# WS2812B-HueStrip-single.net
KiCad netlist of a schematic drawn in EAGLE
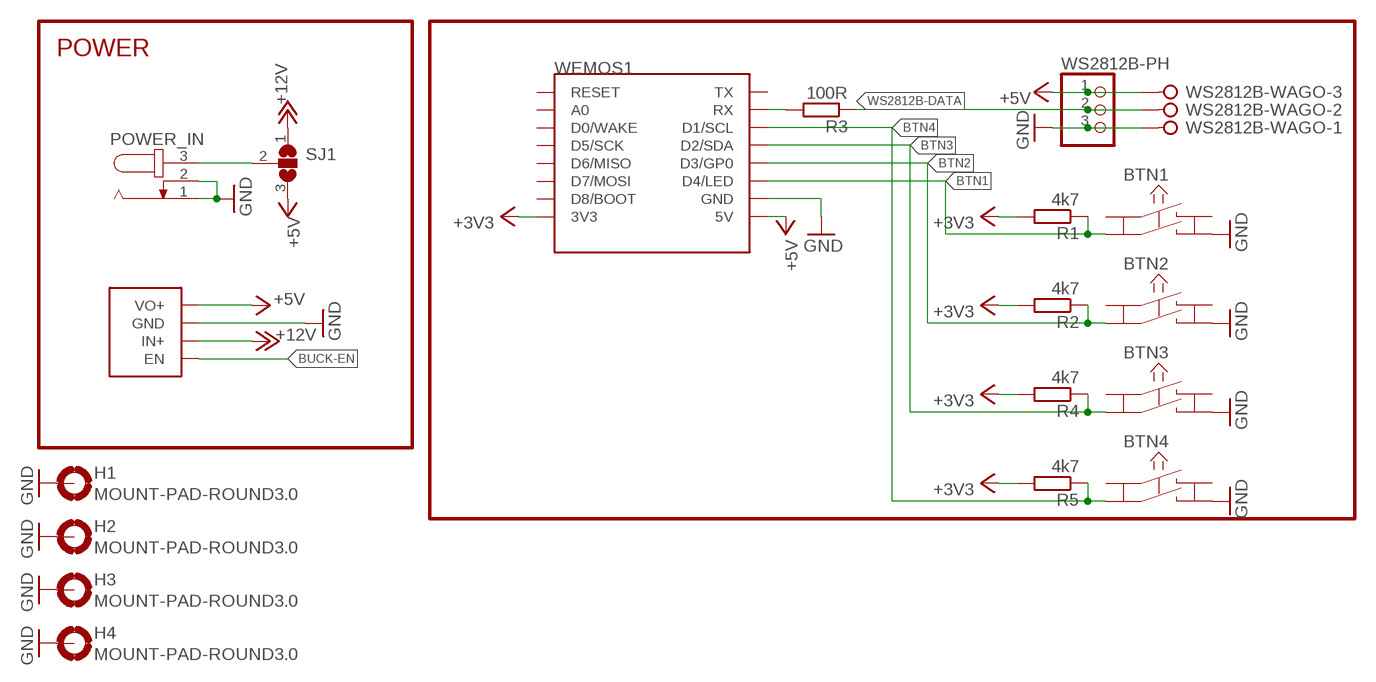
[diagram p0: schematic, sheet 1]

(export (version "E")
  (design (tool "Eeschema 10.0.6"))
  (components
    (comp (ref "BTN1")
      (value "KSM611A")
      (footprint "eagle-import:KSM611A")
      (libsource (lib "eagle-import") (part "KSM611A"))
    )
    (comp (ref "BTN2")
      (value "KSM611A")
      (footprint "eagle-import:KSM611A")
      (libsource (lib "eagle-import") (part "KSM611A"))
    )
    (comp (ref "BTN3")
      (value "KSM611A")
      (footprint "eagle-import:KSM611A")
      (libsource (lib "eagle-import") (part "KSM611A"))
    )
    (comp (ref "BTN4")
      (value "KSM611A")
      (footprint "eagle-import:KSM611A")
      (libsource (lib "eagle-import") (part "KSM611A"))
    )
    (comp (ref "H1")
      (value "MOUNT-PAD-ROUND3.0")
      (footprint "eagle-import:3,0-PAD")
      (libsource (lib "eagle-import") (part "MOUNT-PAD-ROUND3.0"))
    )
    (comp (ref "H2")
      (value "MOUNT-PAD-ROUND3.0")
      (footprint "eagle-import:3,0-PAD")
      (libsource (lib "eagle-import") (part "MOUNT-PAD-ROUND3.0"))
    )
    (comp (ref "H3")
      (value "MOUNT-PAD-ROUND3.0")
      (footprint "eagle-import:3,0-PAD")
      (libsource (lib "eagle-import") (part "MOUNT-PAD-ROUND3.0"))
    )
    (comp (ref "H4")
      (value "MOUNT-PAD-ROUND3.0")
      (footprint "eagle-import:3,0-PAD")
      (libsource (lib "eagle-import") (part "MOUNT-PAD-ROUND3.0"))
    )
    (comp (ref "POWER_IN")
      (value "RAPC7120")
      (footprint "eagle-import:RAPC712")
      (libsource (lib "eagle-import") (part "RAPC7120"))
    )
    (comp (ref "R1")
      (value "4k7")
      (footprint "eagle-import:0204_7")
      (libsource (lib "eagle-import") (part "R-EU_0204/7"))
    )
    (comp (ref "R2")
      (value "4k7")
      (footprint "eagle-import:0204_7")
      (libsource (lib "eagle-import") (part "R-EU_0204/7"))
    )
    (comp (ref "R3")
      (value "100R")
      (footprint "eagle-import:0204_7")
      (libsource (lib "eagle-import") (part "R-EU_0204/7"))
    )
    (comp (ref "R4")
      (value "4k7")
      (footprint "eagle-import:0204_7")
      (libsource (lib "eagle-import") (part "R-EU_0204/7"))
    )
    (comp (ref "R5")
      (value "4k7")
      (footprint "eagle-import:0204_7")
      (libsource (lib "eagle-import") (part "R-EU_0204/7"))
    )
    (comp (ref "SJ1")
      (value "SJ2WW")
      (footprint "eagle-import:SJ_2W")
      (libsource (lib "eagle-import") (part "SJ2WW"))
    )
    (comp (ref "U$1")
      (value "BUCK_CONVERTER_TE818")
      (footprint "eagle-import:BUCK_CONVERTER_TE818")
      (libsource (lib "eagle-import") (part "BUCK_CONVERTER_TE818"))
    )
    (comp (ref "WEMOS1")
      (value "WEMOS-D1-MINI")
      (footprint "eagle-import:WEMOS-D1-MINI")
      (libsource (lib "eagle-import") (part "WEMOS-D1-MINI"))
    )
    (comp (ref "WS2812B-PH")
      (value "PINHD-1X03_2.54-S")
      (footprint "eagle-import:1X03-S")
      (libsource (lib "eagle-import") (part "PINHD-1X03_2.54-S"))
    )
    (comp (ref "WS2812B-WAGO")
      (value "W237-3E")
      (footprint "eagle-import:W237-3E")
      (libsource (lib "eagle-import") (part "W237-3E"))
    )
  )
  (nets
    (net (code "1") (name "+3V3") (class "Default")
      (node (ref "R1") (pin "2") (pinfunction "2_2") (pintype "passive"))
      (node (ref "R2") (pin "2") (pinfunction "2_2") (pintype "passive"))
      (node (ref "R4") (pin "2") (pinfunction "2_2") (pintype "passive"))
      (node (ref "R5") (pin "2") (pinfunction "2_2") (pintype "passive"))
      (node (ref "WEMOS1") (pin "3V3") (pinfunction "3V3_3V3") (pintype "bidirectional"))
    )
    (net (code "2") (name "+5V") (class "Default")
      (node (ref "SJ1") (pin "3") (pinfunction "3_3") (pintype "passive"))
      (node (ref "U$1") (pin "VO+") (pinfunction "VO+_VO+") (pintype "bidirectional"))
      (node (ref "WEMOS1") (pin "5V") (pinfunction "5V_5V") (pintype "bidirectional"))
      (node (ref "WS2812B-PH") (pin "1") (pinfunction "1_1") (pintype "passive"))
      (node (ref "WS2812B-WAGO") (pin "3") (pinfunction "KL_3") (pintype "passive"))
    )
    (net (code "3") (name "+12V") (class "Default")
      (node (ref "SJ1") (pin "1") (pinfunction "1_1") (pintype "passive"))
      (node (ref "U$1") (pin "IN+") (pinfunction "IN+_IN+") (pintype "bidirectional"))
    )
    (net (code "4") (name "BTN1") (class "Default")
      (node (ref "BTN1") (pin "C") (pinfunction "C_C") (pintype "passive"))
      (node (ref "R1") (pin "1") (pinfunction "1_1") (pintype "passive"))
      (node (ref "WEMOS1") (pin "D4") (pinfunction "D4/LED_D4") (pintype "bidirectional"))
    )
    (net (code "5") (name "BTN2") (class "Default")
      (node (ref "BTN2") (pin "C") (pinfunction "C_C") (pintype "passive"))
      (node (ref "R2") (pin "1") (pinfunction "1_1") (pintype "passive"))
      (node (ref "WEMOS1") (pin "D3") (pinfunction "D3/GP0_D3") (pintype "bidirectional"))
    )
    (net (code "6") (name "BTN3") (class "Default")
      (node (ref "BTN3") (pin "C") (pinfunction "C_C") (pintype "passive"))
      (node (ref "R4") (pin "1") (pinfunction "1_1") (pintype "passive"))
      (node (ref "WEMOS1") (pin "D2") (pinfunction "D2/SDA_D2") (pintype "bidirectional"))
    )
    (net (code "7") (name "BTN4") (class "Default")
      (node (ref "BTN4") (pin "C") (pinfunction "C_C") (pintype "passive"))
      (node (ref "R5") (pin "1") (pinfunction "1_1") (pintype "passive"))
      (node (ref "WEMOS1") (pin "D1") (pinfunction "D1/SCL_D1") (pintype "bidirectional"))
    )
    (net (code "8") (name "BUCK-EN") (class "Default")
      (node (ref "U$1") (pin "EN") (pinfunction "EN_EN") (pintype "bidirectional"))
    )
    (net (code "9") (name "GND") (class "Default")
      (node (ref "BTN1") (pin "D") (pinfunction "D_D") (pintype "passive"))
      (node (ref "BTN2") (pin "D") (pinfunction "D_D") (pintype "passive"))
      (node (ref "BTN3") (pin "D") (pinfunction "D_D") (pintype "passive"))
      (node (ref "BTN4") (pin "D") (pinfunction "D_D") (pintype "passive"))
      (node (ref "H1") (pin "B3,0") (pinfunction "MOUNT_B3,0") (pintype "passive"))
      (node (ref "H2") (pin "B3,0") (pinfunction "MOUNT_B3,0") (pintype "passive"))
      (node (ref "H3") (pin "B3,0") (pinfunction "MOUNT_B3,0") (pintype "passive"))
      (node (ref "H4") (pin "B3,0") (pinfunction "MOUNT_B3,0") (pintype "passive"))
      (node (ref "POWER_IN") (pin "1") (pinfunction "1_1") (pintype "passive"))
      (node (ref "POWER_IN") (pin "2") (pinfunction "2_2") (pintype "passive"))
      (node (ref "U$1") (pin "GND") (pinfunction "GND_GND") (pintype "bidirectional"))
      (node (ref "WEMOS1") (pin "GND") (pinfunction "GND_GND") (pintype "bidirectional"))
      (node (ref "WS2812B-PH") (pin "3") (pinfunction "3_3") (pintype "passive"))
      (node (ref "WS2812B-WAGO") (pin "1") (pinfunction "KL_1") (pintype "passive"))
    )
    (net (code "10") (name "Net-(POWER_IN-Pad3)") (class "Default")
      (node (ref "POWER_IN") (pin "3") (pinfunction "3_3") (pintype "passive"))
      (node (ref "SJ1") (pin "2") (pinfunction "2_2") (pintype "passive"))
    )
    (net (code "11") (name "Net-(R3-Pad2)") (class "Default")
      (node (ref "R3") (pin "2") (pinfunction "2_2") (pintype "passive"))
      (node (ref "WEMOS1") (pin "RX") (pinfunction "RX_RX") (pintype "bidirectional"))
    )
    (net (code "12") (name "WS2812B-DATA") (class "Default")
      (node (ref "R3") (pin "1") (pinfunction "1_1") (pintype "passive"))
      (node (ref "WS2812B-PH") (pin "2") (pinfunction "2_2") (pintype "passive"))
      (node (ref "WS2812B-WAGO") (pin "2") (pinfunction "KL_2") (pintype "passive"))
    )
    (net (code "13") (name "unconnected-(BTN1-PadA)") (class "Default")
      (node (ref "BTN1") (pin "A") (pinfunction "A_A") (pintype "passive"))
    )
    (net (code "14") (name "unconnected-(BTN1-PadB)") (class "Default")
      (node (ref "BTN1") (pin "B") (pinfunction "B_B") (pintype "passive"))
    )
    (net (code "15") (name "unconnected-(BTN2-PadA)") (class "Default")
      (node (ref "BTN2") (pin "A") (pinfunction "A_A") (pintype "passive"))
    )
    (net (code "16") (name "unconnected-(BTN2-PadB)") (class "Default")
      (node (ref "BTN2") (pin "B") (pinfunction "B_B") (pintype "passive"))
    )
    (net (code "17") (name "unconnected-(BTN3-PadA)") (class "Default")
      (node (ref "BTN3") (pin "A") (pinfunction "A_A") (pintype "passive"))
    )
    (net (code "18") (name "unconnected-(BTN3-PadB)") (class "Default")
      (node (ref "BTN3") (pin "B") (pinfunction "B_B") (pintype "passive"))
    )
    (net (code "19") (name "unconnected-(BTN4-PadA)") (class "Default")
      (node (ref "BTN4") (pin "A") (pinfunction "A_A") (pintype "passive"))
    )
    (net (code "20") (name "unconnected-(BTN4-PadB)") (class "Default")
      (node (ref "BTN4") (pin "B") (pinfunction "B_B") (pintype "passive"))
    )
    (net (code "21") (name "unconnected-(WEMOS1-D0{slash}WAKE-PadD0)") (class "Default")
      (node (ref "WEMOS1") (pin "D0") (pinfunction "D0/WAKE_D0") (pintype "bidirectional"))
    )
    (net (code "22") (name "unconnected-(WEMOS1-D5{slash}SCK-PadD5)") (class "Default")
      (node (ref "WEMOS1") (pin "D5") (pinfunction "D5/SCK_D5") (pintype "bidirectional"))
    )
    (net (code "23") (name "unconnected-(WEMOS1-D6{slash}MISO-PadD6)") (class "Default")
      (node (ref "WEMOS1") (pin "D6") (pinfunction "D6/MISO_D6") (pintype "bidirectional"))
    )
    (net (code "24") (name "unconnected-(WEMOS1-D7{slash}MOSI-PadD7)") (class "Default")
      (node (ref "WEMOS1") (pin "D7") (pinfunction "D7/MOSI_D7") (pintype "bidirectional"))
    )
    (net (code "25") (name "unconnected-(WEMOS1-D8{slash}BOOT-PadD8)") (class "Default")
      (node (ref "WEMOS1") (pin "D8") (pinfunction "D8/BOOT_D8") (pintype "bidirectional"))
    )
    (net (code "26") (name "unconnected-(WEMOS1-PadA0)") (class "Default")
      (node (ref "WEMOS1") (pin "A0") (pinfunction "A0_A0") (pintype "bidirectional"))
    )
    (net (code "27") (name "unconnected-(WEMOS1-PadRESET)") (class "Default")
      (node (ref "WEMOS1") (pin "RESET") (pinfunction "RESET_RESET") (pintype "bidirectional"))
    )
    (net (code "28") (name "unconnected-(WEMOS1-PadTX)") (class "Default")
      (node (ref "WEMOS1") (pin "TX") (pinfunction "TX_TX") (pintype "bidirectional"))
    )
  )
)
